# Sheet1.net
KiCad netlist of a schematic drawn in Altium Designer
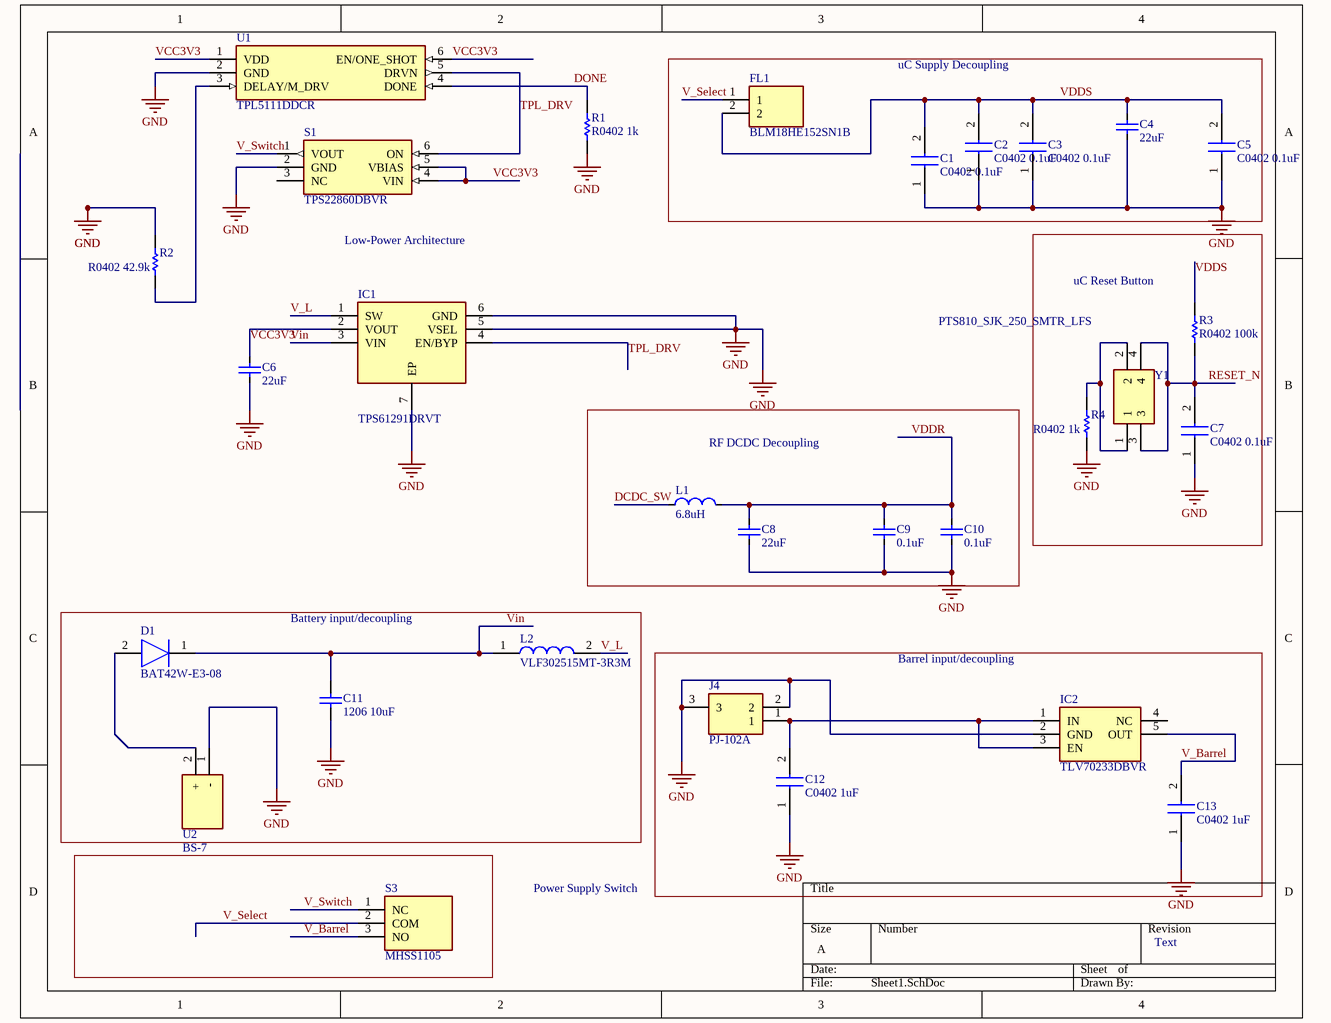
[diagram p0: Sheet1.SchDoc]

(export (version "E")
  (design (tool "Eeschema 10.0.6"))
  (components
    (comp (ref "C1")
      (value "C0402 0.1uF")
      (footprint "SamacSys:CAPC0603X33N")
      (description "Capacitor")
      (fields
        (field (name "MANUFACTURER_PART_NUMBER") "02014D474MAT2A")
        (field (name "MOUSER PART NUMBER") "581-02014D474MAT2A")
      )
      (libsource (lib "*") (part "02014D474MAT2A"))
    )
    (comp (ref "C2")
      (value "C0402 0.1uF")
      (footprint "SamacSys:CAPC0603X33N")
      (description "Capacitor")
      (fields
        (field (name "MANUFACTURER_PART_NUMBER") "02014D474MAT2A")
        (field (name "MOUSER PART NUMBER") "581-02014D474MAT2A")
      )
      (libsource (lib "*") (part "02014D474MAT2A"))
    )
    (comp (ref "C3")
      (value "C0402 0.1uF")
      (footprint "SamacSys:CAPC0603X33N")
      (description "Capacitor")
      (fields
        (field (name "MANUFACTURER_PART_NUMBER") "02014D474MAT2A")
        (field (name "MOUSER PART NUMBER") "581-02014D474MAT2A")
      )
      (libsource (lib "*") (part "02014D474MAT2A"))
    )
    (comp (ref "C4")
      (value "22uF")
      (footprint "PASSIVE-CAPACITOR-0603")
      (description "Generic Capacitor")
      (libsource (lib "MasterLib") (part "Passive-Capacitor (Generic)"))
    )
    (comp (ref "C5")
      (value "C0402 0.1uF")
      (footprint "SamacSys:CAPC0603X33N")
      (description "Capacitor")
      (fields
        (field (name "MANUFACTURER_PART_NUMBER") "02014D474MAT2A")
        (field (name "MOUSER PART NUMBER") "581-02014D474MAT2A")
      )
      (libsource (lib "*") (part "02014D474MAT2A"))
    )
    (comp (ref "C6")
      (value "22uF")
      (footprint "PASSIVE-CAPACITOR-0603")
      (description "Generic Capacitor")
      (fields (field (name "Comment") "Passive-Capacitor (Generic)"))
      (libsource (lib "") (part "Passive-Capacitor (Generic)_1"))
    )
    (comp (ref "C7")
      (value "C0402 0.1uF")
      (footprint "SamacSys:CAPC0603X33N")
      (description "Capacitor")
      (fields
        (field (name "MANUFACTURER_PART_NUMBER") "02014D474MAT2A")
        (field (name "MOUSER PART NUMBER") "581-02014D474MAT2A")
      )
      (libsource (lib "*") (part "02014D474MAT2A"))
    )
    (comp (ref "C8")
      (value "22uF")
      (footprint "PASSIVE-CAPACITOR-0603")
      (description "Generic Capacitor")
      (libsource (lib "MasterLib") (part "Passive-Capacitor (Generic)"))
    )
    (comp (ref "C9")
      (value "0.1uF")
      (footprint "PASSIVE-CAPACITOR-0603")
      (description "Generic Capacitor")
      (fields (field (name "Comment") "Passive-Capacitor (Generic)"))
      (libsource (lib "") (part "Passive-Capacitor (Generic)_1"))
    )
    (comp (ref "C10")
      (value "0.1uF")
      (footprint "PASSIVE-CAPACITOR-0603")
      (description "Generic Capacitor")
      (fields (field (name "Comment") "Passive-Capacitor (Generic)"))
      (libsource (lib "") (part "Passive-Capacitor (Generic)_1"))
    )
    (comp (ref "C11")
      (value "1206 10uF")
      (footprint "KEMT-1206-2_M")
      (description "CAP, Ceramic, 0.1 uF, +/- 10%, 50 V, -55 to 125 degC, 1206 (3216 Metric), RoHS, Tape and Reel")
      (fields (field (name "MANUFACTURER") "Kemet"))
      (libsource (lib "Altium Content Vault") (part "CAP-NP-2"))
    )
    (comp (ref "C12")
      (value "C0402 1uF")
      (footprint "SamacSys:CAPC0603X33N")
      (description "Capacitor")
      (fields
        (field (name "MANUFACTURER_PART_NUMBER") "02014D474MAT2A")
        (field (name "MOUSER PART NUMBER") "581-02014D474MAT2A")
      )
      (libsource (lib "*") (part "02014D474MAT2A"))
    )
    (comp (ref "C13")
      (value "C0402 1uF")
      (footprint "SamacSys:CAPC0603X33N")
      (description "Capacitor")
      (fields
        (field (name "MANUFACTURER_PART_NUMBER") "02014D474MAT2A")
        (field (name "MOUSER PART NUMBER") "581-02014D474MAT2A")
      )
      (libsource (lib "*") (part "02014D474MAT2A"))
    )
    (comp (ref "D1")
      (value "BAT42W-E3-08")
      (footprint "SamacSys:SOD3716X135N")
      (description "Diode")
      (fields
        (field (name "MOUSER PART NUMBER") "78-BAT42W-E3-08")
        (field (name "RS PART NUMBER") "1808601P")
      )
      (libsource (lib "*") (part "BAT42W-E3-08"))
    )
    (comp (ref "FL1")
      (value "BLM18HE152SN1B")
      (footprint "SamacSys:BEADC1608X95N")
      (description "Filter")
      (libsource (lib "*") (part "BLM18HE152SN1B"))
    )
    (comp (ref "IC1")
      (value "TPS61291DRVT")
      (footprint "SON65P200X200X80-7N")
      (description "Integrated Circuit")
      (fields
        (field (name "MOUSER PART NUMBER") "595-TPS61291DRVT")
        (field (name "RS PART NUMBER") "9143112P")
      )
      (libsource (lib "Enviornmental_Sensor") (part "TPS61291DRVT"))
    )
    (comp (ref "IC2")
      (value "TLV70233DBVR")
      (footprint "SamacSys:SOT95P280X145-5N")
      (description "Integrated Circuit")
      (fields (field (name "MOUSER PART NUMBER") "595-TLV70233DBVR"))
      (libsource (lib "*") (part "TLV70233DBVR"))
    )
    (comp (ref "J4")
      (value "PJ-102A")
      (footprint "PJ-102AH")
      (description "Connector")
      (fields (field (name "MOUSER PART NUMBER") "490-PJ-102A"))
      (libsource (lib "Enviornmental_Sensor") (part "PJ-102A"))
    )
    (comp (ref "L1")
      (value "6.8uH")
      (footprint "PASSIVE-INDUCTOR-0603")
      (description "Generic Inductor")
      (fields (field (name "Comment") "Passive-Inductor (Generic)"))
      (libsource (lib "MasterLib") (part "Passive-Inductor (Generic)"))
    )
    (comp (ref "L2")
      (value "VLF302515MT-3R3M")
      (footprint "SamacSys:VLF302515MT")
      (description "Inductor")
      (fields (field (name "MOUSER PART NUMBER") "810-VLF302515MT-3R3M"))
      (libsource (lib "*") (part "VLF302515MT-3R3M"))
    )
    (comp (ref "R1")
      (value "R0402 1k")
      (footprint "RESC1005X40X25NL05T05")
      (fields (field (name "MANUFACTURER") "Vishay Dale") (field (name "PART NUMBER") "CRCW040210K0FKED"))
      (libsource (lib "Altium Content Vault") (part "RES"))
    )
    (comp (ref "R2")
      (value "R0402 42.9k")
      (footprint "RESC1005X40X25NL05T05")
      (fields (field (name "MANUFACTURER") "Vishay Dale") (field (name "PART NUMBER") "CRCW040210K0FKED"))
      (libsource (lib "Altium Content Vault") (part "RES"))
    )
    (comp (ref "R3")
      (value "R0402 100k")
      (footprint "RESC1005X40X25NL05T05")
      (fields (field (name "MANUFACTURER") "Vishay Dale") (field (name "PART NUMBER") "CRCW040210K0FKED"))
      (libsource (lib "Altium Content Vault") (part "RES"))
    )
    (comp (ref "R4")
      (value "R0402 1k")
      (footprint "RESC1005X40X25NL05T05")
      (fields (field (name "MANUFACTURER") "Vishay Dale") (field (name "PART NUMBER") "CRCW040210K0FKED"))
      (libsource (lib "Altium Content Vault") (part "RES"))
    )
    (comp (ref "S1")
      (value "TPS22860DBVR")
      (footprint "SOT95P280X145-6N")
      (description "Switch")
      (fields (field (name "MOUSER PART NUMBER") "595-TPS22860DBVR"))
      (libsource (lib "Enviornmental_Sensor") (part "TPS22860DBVR"))
    )
    (comp (ref "S3")
      (value "MHSS1105")
      (footprint "MHSS1105")
      (description "Switch")
      (fields (field (name "MOUSER PART NUMBER") "642-MHSS1105"))
      (libsource (lib "Enviornmental_Sensor") (part "MHSS1105"))
    )
    (comp (ref "U1")
      (value "TPL5111DDCR")
      (footprint "SOT95P280X110-6N")
      (description "Undefined or Miscellaneous")
      (fields (field (name "MOUSER PART NUMBER") "595-TPL5111DDCR"))
      (libsource (lib "Enviornmental_Sensor") (part "TPL5111DDCR"))
    )
    (comp (ref "U2")
      (value "BS-7")
      (footprint "BS7")
      (description "Undefined or Miscellaneous")
      (libsource (lib "Enviornmental_Sensor") (part "BS-7"))
    )
    (comp (ref "Y1")
      (value "PTS810_SJK_250_SMTR_LFS")
      (footprint "SamacSys:PTS810SJK250SMTRLFS")
      (description "Crystal or Oscillator")
      (fields
        (field (name "MANUFACTURER_PART_NUMBER") "PTS810 SJK 250 SMTR LFS")
        (field (name "MOUSER PART NUMBER") "611-PTS810SJK250SMTR")
      )
      (libsource (lib "*") (part "PTS810_SJK_250_SMTR_LFS"))
    )
  )
  (nets
    (net (code "1") (name "/DCDC_SW") (class "Default")
      (node (ref "L1") (pin "1") (pinfunction "1_1") (pintype "passive"))
    )
    (net (code "2") (name "/DONE") (class "Default")
      (node (ref "R1") (pin "2") (pinfunction "2_2") (pintype "passive"))
      (node (ref "U1") (pin "4") (pinfunction "DONE_4") (pintype "input"))
    )
    (net (code "3") (name "/RESET_N") (class "Default")
      (node (ref "C7") (pin "2") (pinfunction "2_2") (pintype "passive"))
      (node (ref "R3") (pin "1") (pinfunction "1_1") (pintype "passive"))
      (node (ref "Y1") (pin "3") (pinfunction "3_3") (pintype "passive"))
      (node (ref "Y1") (pin "4") (pinfunction "4_4") (pintype "passive"))
    )
    (net (code "4") (name "/TPL_DRV") (class "Default")
      (node (ref "IC1") (pin "4") (pinfunction "EN/BYP_4") (pintype "passive"))
      (node (ref "S1") (pin "6") (pinfunction "ON_6") (pintype "input"))
      (node (ref "U1") (pin "5") (pinfunction "DRVN_5") (pintype "output"))
    )
    (net (code "5") (name "/VCC3V3") (class "Default")
      (node (ref "C6") (pin "2") (pinfunction "2_2") (pintype "passive"))
      (node (ref "IC1") (pin "2") (pinfunction "VOUT_2") (pintype "passive"))
      (node (ref "S1") (pin "4") (pinfunction "VIN_4") (pintype "input"))
      (node (ref "S1") (pin "5") (pinfunction "VBIAS_5") (pintype "input"))
      (node (ref "U1") (pin "1") (pinfunction "VDD_1") (pintype "power_in"))
      (node (ref "U1") (pin "6") (pinfunction "EN/ONE_SHOT_6") (pintype "input"))
    )
    (net (code "6") (name "/VDDR") (class "Default")
      (node (ref "C10") (pin "2") (pinfunction "2_2") (pintype "passive"))
      (node (ref "C8") (pin "1") (pinfunction "1_1") (pintype "passive"))
      (node (ref "C9") (pin "2") (pinfunction "2_2") (pintype "passive"))
      (node (ref "L1") (pin "2") (pinfunction "2_2") (pintype "passive"))
    )
    (net (code "7") (name "/VDDS") (class "Default")
      (node (ref "C1") (pin "2") (pinfunction "2_2") (pintype "passive"))
      (node (ref "C2") (pin "2") (pinfunction "2_2") (pintype "passive"))
      (node (ref "C3") (pin "2") (pinfunction "2_2") (pintype "passive"))
      (node (ref "C4") (pin "1") (pinfunction "1_1") (pintype "passive"))
      (node (ref "C5") (pin "2") (pinfunction "2_2") (pintype "passive"))
      (node (ref "FL1") (pin "2") (pinfunction "2_2") (pintype "passive"))
      (node (ref "R3") (pin "2") (pinfunction "2_2") (pintype "passive"))
    )
    (net (code "8") (name "/V_Barrel") (class "Default")
      (node (ref "C13") (pin "2") (pinfunction "2_2") (pintype "passive"))
      (node (ref "IC2") (pin "5") (pinfunction "OUT_5") (pintype "passive"))
      (node (ref "S3") (pin "3") (pinfunction "NO_3") (pintype "passive"))
    )
    (net (code "9") (name "/V_L") (class "Default")
      (node (ref "IC1") (pin "1") (pinfunction "SW_1") (pintype "passive"))
      (node (ref "L2") (pin "2") (pinfunction "2_2") (pintype "passive"))
    )
    (net (code "10") (name "/V_Select") (class "Default")
      (node (ref "FL1") (pin "1") (pinfunction "1_1") (pintype "passive"))
      (node (ref "S3") (pin "2") (pinfunction "COM_2") (pintype "passive"))
    )
    (net (code "11") (name "/V_Switch") (class "Default")
      (node (ref "S1") (pin "1") (pinfunction "VOUT_1") (pintype "output"))
      (node (ref "S3") (pin "1") (pinfunction "NC_1") (pintype "passive"))
    )
    (net (code "12") (name "/Vin") (class "Default")
      (node (ref "C11") (pin "2") (pinfunction "2_2") (pintype "passive"))
      (node (ref "D1") (pin "1") (pinfunction "K_1") (pintype "passive"))
      (node (ref "IC1") (pin "3") (pinfunction "VIN_3") (pintype "passive"))
      (node (ref "L2") (pin "1") (pinfunction "1_1") (pintype "passive"))
    )
    (net (code "13") (name "GND") (class "Default")
      (node (ref "C1") (pin "1") (pinfunction "1_1") (pintype "passive"))
      (node (ref "C10") (pin "1") (pinfunction "1_1") (pintype "passive"))
      (node (ref "C11") (pin "1") (pinfunction "1_1") (pintype "passive"))
      (node (ref "C12") (pin "1") (pinfunction "1_1") (pintype "passive"))
      (node (ref "C13") (pin "1") (pinfunction "1_1") (pintype "passive"))
      (node (ref "C2") (pin "1") (pinfunction "1_1") (pintype "passive"))
      (node (ref "C3") (pin "1") (pinfunction "1_1") (pintype "passive"))
      (node (ref "C4") (pin "2") (pinfunction "2_2") (pintype "passive"))
      (node (ref "C5") (pin "1") (pinfunction "1_1") (pintype "passive"))
      (node (ref "C6") (pin "1") (pinfunction "1_1") (pintype "passive"))
      (node (ref "C7") (pin "1") (pinfunction "1_1") (pintype "passive"))
      (node (ref "C8") (pin "2") (pinfunction "2_2") (pintype "passive"))
      (node (ref "C9") (pin "1") (pinfunction "1_1") (pintype "passive"))
      (node (ref "IC1") (pin "5") (pinfunction "VSEL_5") (pintype "passive"))
      (node (ref "IC1") (pin "6") (pinfunction "GND_6") (pintype "passive"))
      (node (ref "IC1") (pin "7") (pinfunction "EP_7") (pintype "passive"))
      (node (ref "IC2") (pin "2") (pinfunction "GND_2") (pintype "passive"))
      (node (ref "J4") (pin "2") (pinfunction "2_2") (pintype "passive"))
      (node (ref "J4") (pin "3") (pinfunction "3_3") (pintype "passive"))
      (node (ref "R1") (pin "1") (pinfunction "1_1") (pintype "passive"))
      (node (ref "R2") (pin "2") (pinfunction "2_2") (pintype "passive"))
      (node (ref "R4") (pin "1") (pinfunction "1_1") (pintype "passive"))
      (node (ref "S1") (pin "2") (pinfunction "GND_2") (pintype "power_in"))
      (node (ref "U1") (pin "2") (pinfunction "GND_2") (pintype "power_in"))
      (node (ref "U2") (pin "1") (pinfunction "-_1") (pintype "passive"))
    )
    (net (code "14") (name "Net-(D1-A)") (class "Default")
      (node (ref "D1") (pin "2") (pinfunction "A_2") (pintype "passive"))
      (node (ref "U2") (pin "2") (pinfunction "+_2") (pintype "passive"))
    )
    (net (code "15") (name "Net-(IC2-EN)") (class "Default")
      (node (ref "C12") (pin "2") (pinfunction "2_2") (pintype "passive"))
      (node (ref "IC2") (pin "1") (pinfunction "IN_1") (pintype "passive"))
      (node (ref "IC2") (pin "3") (pinfunction "EN_3") (pintype "passive"))
      (node (ref "J4") (pin "1") (pinfunction "1_1") (pintype "passive"))
    )
    (net (code "16") (name "Net-(R4-Pad2)") (class "Default")
      (node (ref "R4") (pin "2") (pinfunction "2_2") (pintype "passive"))
      (node (ref "Y1") (pin "1") (pinfunction "1_1") (pintype "passive"))
      (node (ref "Y1") (pin "2") (pinfunction "2_2") (pintype "passive"))
    )
    (net (code "17") (name "Net-(U1-DELAY{slash}M_DRV)") (class "Default")
      (node (ref "R2") (pin "1") (pinfunction "1_1") (pintype "passive"))
      (node (ref "U1") (pin "3") (pinfunction "DELAY/M_DRV_3") (pintype "input"))
    )
    (net (code "18") (name "unconnected-(IC2-NC-Pad4)") (class "Default")
      (node (ref "IC2") (pin "4") (pinfunction "NC_4") (pintype "passive"))
    )
    (net (code "19") (name "unconnected-(S1-NC-Pad3)") (class "Default")
      (node (ref "S1") (pin "3") (pinfunction "NC_3") (pintype "passive"))
    )
  )
)
